# Microcontroller_Schematic.net
KiCad netlist of a schematic drawn in Altium Designer
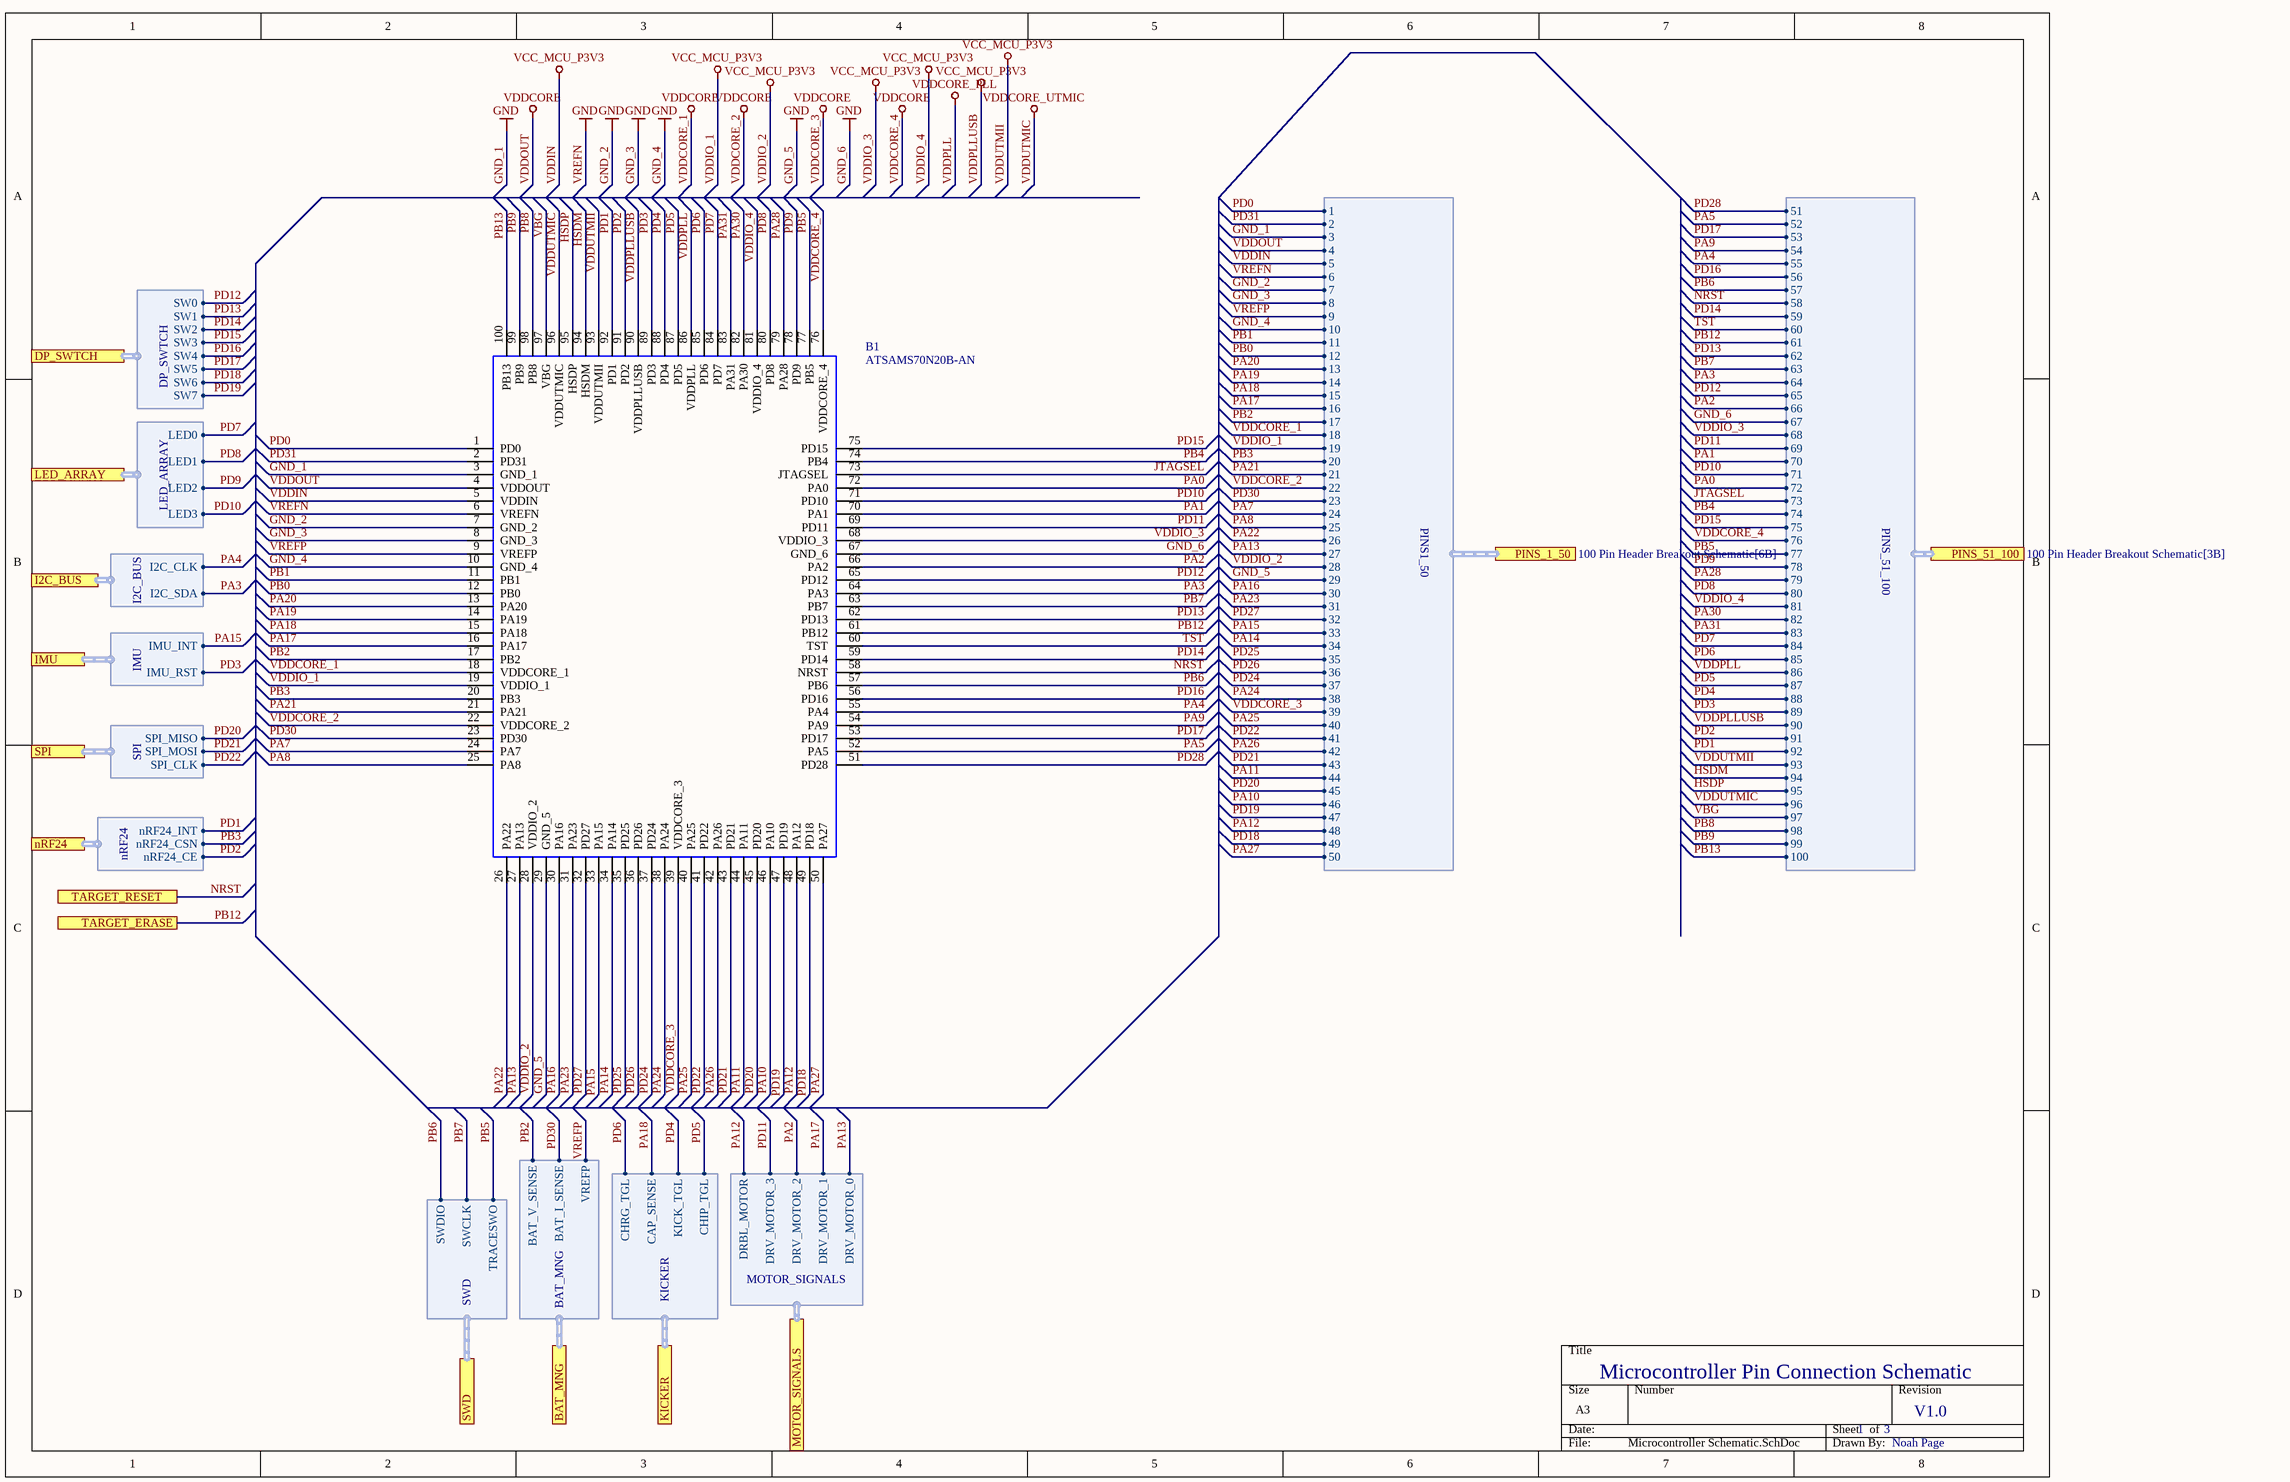
[diagram p0: Microcontroller Schematic.SchDoc]

(export (version "E")
  (design (tool "Eeschema 10.0.6"))
  (components
    (comp (ref "B1")
      (value "ATSAMS70N20B-AN")
      (footprint "QFP50P1600X1600X160-100N")
      (description "ARM Microcontrollers - MCU CM7,1024kB Flash,384kB SRAM,LQFP100")
      (fields (field (name "MOUSER PART NUMBER") "556-ATSAMS70N20B-AN"))
      (libsource (lib "Schematic Library") (part "ATSAMS70N20B-AN"))
    )
  )
  (nets
    (net (code "13") (name "/HSDM") (class "Default")
      (node (ref "B1") (pin "94") (pinfunction "HSDM_94") (pintype "passive"))
    )
    (net (code "14") (name "/HSDP") (class "Default")
      (node (ref "B1") (pin "95") (pinfunction "HSDP_95") (pintype "passive"))
    )
    (net (code "15") (name "/JTAGSEL") (class "Default")
      (node (ref "B1") (pin "73") (pinfunction "JTAGSEL_73") (pintype "passive"))
    )
    (net (code "16") (name "/NRST") (class "Default")
      (node (ref "B1") (pin "58") (pinfunction "NRST_58") (pintype "passive"))
    )
    (net (code "17") (name "/PA0") (class "Default")
      (node (ref "B1") (pin "72") (pinfunction "PA0_72") (pintype "passive"))
    )
    (net (code "18") (name "/PA1") (class "Default")
      (node (ref "B1") (pin "70") (pinfunction "PA1_70") (pintype "passive"))
    )
    (net (code "19") (name "/PA2") (class "Default")
      (node (ref "B1") (pin "66") (pinfunction "PA2_66") (pintype "passive"))
    )
    (net (code "20") (name "/PA3") (class "Default")
      (node (ref "B1") (pin "64") (pinfunction "PA3_64") (pintype "passive"))
    )
    (net (code "21") (name "/PA4") (class "Default")
      (node (ref "B1") (pin "55") (pinfunction "PA4_55") (pintype "passive"))
    )
    (net (code "22") (name "/PA5") (class "Default")
      (node (ref "B1") (pin "52") (pinfunction "PA5_52") (pintype "passive"))
    )
    (net (code "23") (name "/PA7") (class "Default")
      (node (ref "B1") (pin "24") (pinfunction "PA7_24") (pintype "passive"))
    )
    (net (code "24") (name "/PA8") (class "Default")
      (node (ref "B1") (pin "25") (pinfunction "PA8_25") (pintype "passive"))
    )
    (net (code "25") (name "/PA9") (class "Default")
      (node (ref "B1") (pin "54") (pinfunction "PA9_54") (pintype "passive"))
    )
    (net (code "26") (name "/PA10") (class "Default")
      (node (ref "B1") (pin "46") (pinfunction "PA10_46") (pintype "passive"))
    )
    (net (code "27") (name "/PA11") (class "Default")
      (node (ref "B1") (pin "44") (pinfunction "PA11_44") (pintype "passive"))
    )
    (net (code "28") (name "/PA12") (class "Default")
      (node (ref "B1") (pin "48") (pinfunction "PA12_48") (pintype "passive"))
    )
    (net (code "29") (name "/PA13") (class "Default")
      (node (ref "B1") (pin "27") (pinfunction "PA13_27") (pintype "passive"))
    )
    (net (code "30") (name "/PA14") (class "Default")
      (node (ref "B1") (pin "34") (pinfunction "PA14_34") (pintype "passive"))
    )
    (net (code "31") (name "/PA15") (class "Default")
      (node (ref "B1") (pin "33") (pinfunction "PA15_33") (pintype "passive"))
    )
    (net (code "32") (name "/PA16") (class "Default")
      (node (ref "B1") (pin "30") (pinfunction "PA16_30") (pintype "passive"))
    )
    (net (code "33") (name "/PA17") (class "Default")
      (node (ref "B1") (pin "16") (pinfunction "PA17_16") (pintype "passive"))
    )
    (net (code "34") (name "/PA18") (class "Default")
      (node (ref "B1") (pin "15") (pinfunction "PA18_15") (pintype "passive"))
    )
    (net (code "35") (name "/PA19") (class "Default")
      (node (ref "B1") (pin "14") (pinfunction "PA19_14") (pintype "passive"))
    )
    (net (code "36") (name "/PA20") (class "Default")
      (node (ref "B1") (pin "13") (pinfunction "PA20_13") (pintype "passive"))
    )
    (net (code "37") (name "/PA21") (class "Default")
      (node (ref "B1") (pin "21") (pinfunction "PA21_21") (pintype "passive"))
    )
    (net (code "38") (name "/PA22") (class "Default")
      (node (ref "B1") (pin "26") (pinfunction "PA22_26") (pintype "passive"))
    )
    (net (code "39") (name "/PA23") (class "Default")
      (node (ref "B1") (pin "31") (pinfunction "PA23_31") (pintype "passive"))
    )
    (net (code "40") (name "/PA24") (class "Default")
      (node (ref "B1") (pin "38") (pinfunction "PA24_38") (pintype "passive"))
    )
    (net (code "41") (name "/PA25") (class "Default")
      (node (ref "B1") (pin "40") (pinfunction "PA25_40") (pintype "passive"))
    )
    (net (code "42") (name "/PA26") (class "Default")
      (node (ref "B1") (pin "42") (pinfunction "PA26_42") (pintype "passive"))
    )
    (net (code "43") (name "/PA27") (class "Default")
      (node (ref "B1") (pin "50") (pinfunction "PA27_50") (pintype "passive"))
    )
    (net (code "44") (name "/PA28") (class "Default")
      (node (ref "B1") (pin "79") (pinfunction "PA28_79") (pintype "passive"))
    )
    (net (code "45") (name "/PA30") (class "Default")
      (node (ref "B1") (pin "82") (pinfunction "PA30_82") (pintype "passive"))
    )
    (net (code "46") (name "/PA31") (class "Default")
      (node (ref "B1") (pin "83") (pinfunction "PA31_83") (pintype "passive"))
    )
    (net (code "47") (name "/PB0") (class "Default")
      (node (ref "B1") (pin "12") (pinfunction "PB0_12") (pintype "passive"))
    )
    (net (code "48") (name "/PB1") (class "Default")
      (node (ref "B1") (pin "11") (pinfunction "PB1_11") (pintype "passive"))
    )
    (net (code "49") (name "/PB2") (class "Default")
      (node (ref "B1") (pin "17") (pinfunction "PB2_17") (pintype "passive"))
    )
    (net (code "50") (name "/PB3") (class "Default")
      (node (ref "B1") (pin "20") (pinfunction "PB3_20") (pintype "passive"))
    )
    (net (code "51") (name "/PB4") (class "Default")
      (node (ref "B1") (pin "74") (pinfunction "PB4_74") (pintype "passive"))
    )
    (net (code "52") (name "/PB5") (class "Default")
      (node (ref "B1") (pin "77") (pinfunction "PB5_77") (pintype "passive"))
    )
    (net (code "53") (name "/PB6") (class "Default")
      (node (ref "B1") (pin "57") (pinfunction "PB6_57") (pintype "passive"))
    )
    (net (code "54") (name "/PB7") (class "Default")
      (node (ref "B1") (pin "63") (pinfunction "PB7_63") (pintype "passive"))
    )
    (net (code "55") (name "/PB8") (class "Default")
      (node (ref "B1") (pin "98") (pinfunction "PB8_98") (pintype "passive"))
    )
    (net (code "56") (name "/PB9") (class "Default")
      (node (ref "B1") (pin "99") (pinfunction "PB9_99") (pintype "passive"))
    )
    (net (code "57") (name "/PB12") (class "Default")
      (node (ref "B1") (pin "61") (pinfunction "PB12_61") (pintype "passive"))
    )
    (net (code "58") (name "/PB13") (class "Default")
      (node (ref "B1") (pin "100") (pinfunction "PB13_100") (pintype "passive"))
    )
    (net (code "59") (name "/PD0") (class "Default")
      (node (ref "B1") (pin "1") (pinfunction "PD0_1") (pintype "passive"))
    )
    (net (code "60") (name "/PD1") (class "Default")
      (node (ref "B1") (pin "92") (pinfunction "PD1_92") (pintype "passive"))
    )
    (net (code "61") (name "/PD2") (class "Default")
      (node (ref "B1") (pin "91") (pinfunction "PD2_91") (pintype "passive"))
    )
    (net (code "62") (name "/PD3") (class "Default")
      (node (ref "B1") (pin "89") (pinfunction "PD3_89") (pintype "passive"))
    )
    (net (code "63") (name "/PD4") (class "Default")
      (node (ref "B1") (pin "88") (pinfunction "PD4_88") (pintype "passive"))
    )
    (net (code "64") (name "/PD5") (class "Default")
      (node (ref "B1") (pin "87") (pinfunction "PD5_87") (pintype "passive"))
    )
    (net (code "65") (name "/PD6") (class "Default")
      (node (ref "B1") (pin "85") (pinfunction "PD6_85") (pintype "passive"))
    )
    (net (code "66") (name "/PD7") (class "Default")
      (node (ref "B1") (pin "84") (pinfunction "PD7_84") (pintype "passive"))
    )
    (net (code "67") (name "/PD8") (class "Default")
      (node (ref "B1") (pin "80") (pinfunction "PD8_80") (pintype "passive"))
    )
    (net (code "68") (name "/PD9") (class "Default")
      (node (ref "B1") (pin "78") (pinfunction "PD9_78") (pintype "passive"))
    )
    (net (code "69") (name "/PD10") (class "Default")
      (node (ref "B1") (pin "71") (pinfunction "PD10_71") (pintype "passive"))
    )
    (net (code "70") (name "/PD11") (class "Default")
      (node (ref "B1") (pin "69") (pinfunction "PD11_69") (pintype "passive"))
    )
    (net (code "71") (name "/PD12") (class "Default")
      (node (ref "B1") (pin "65") (pinfunction "PD12_65") (pintype "passive"))
    )
    (net (code "72") (name "/PD13") (class "Default")
      (node (ref "B1") (pin "62") (pinfunction "PD13_62") (pintype "passive"))
    )
    (net (code "73") (name "/PD14") (class "Default")
      (node (ref "B1") (pin "59") (pinfunction "PD14_59") (pintype "passive"))
    )
    (net (code "74") (name "/PD15") (class "Default")
      (node (ref "B1") (pin "75") (pinfunction "PD15_75") (pintype "passive"))
    )
    (net (code "75") (name "/PD16") (class "Default")
      (node (ref "B1") (pin "56") (pinfunction "PD16_56") (pintype "passive"))
    )
    (net (code "76") (name "/PD17") (class "Default")
      (node (ref "B1") (pin "53") (pinfunction "PD17_53") (pintype "passive"))
    )
    (net (code "77") (name "/PD18") (class "Default")
      (node (ref "B1") (pin "49") (pinfunction "PD18_49") (pintype "passive"))
    )
    (net (code "78") (name "/PD19") (class "Default")
      (node (ref "B1") (pin "47") (pinfunction "PD19_47") (pintype "passive"))
    )
    (net (code "79") (name "/PD20") (class "Default")
      (node (ref "B1") (pin "45") (pinfunction "PD20_45") (pintype "passive"))
    )
    (net (code "80") (name "/PD21") (class "Default")
      (node (ref "B1") (pin "43") (pinfunction "PD21_43") (pintype "passive"))
    )
    (net (code "81") (name "/PD22") (class "Default")
      (node (ref "B1") (pin "41") (pinfunction "PD22_41") (pintype "passive"))
    )
    (net (code "82") (name "/PD24") (class "Default")
      (node (ref "B1") (pin "37") (pinfunction "PD24_37") (pintype "passive"))
    )
    (net (code "83") (name "/PD25") (class "Default")
      (node (ref "B1") (pin "35") (pinfunction "PD25_35") (pintype "passive"))
    )
    (net (code "84") (name "/PD26") (class "Default")
      (node (ref "B1") (pin "36") (pinfunction "PD26_36") (pintype "passive"))
    )
    (net (code "85") (name "/PD27") (class "Default")
      (node (ref "B1") (pin "32") (pinfunction "PD27_32") (pintype "passive"))
    )
    (net (code "86") (name "/PD28") (class "Default")
      (node (ref "B1") (pin "51") (pinfunction "PD28_51") (pintype "passive"))
    )
    (net (code "87") (name "/PD30") (class "Default")
      (node (ref "B1") (pin "23") (pinfunction "PD30_23") (pintype "passive"))
    )
    (net (code "88") (name "/PD31") (class "Default")
      (node (ref "B1") (pin "2") (pinfunction "PD31_2") (pintype "passive"))
    )
    (net (code "89") (name "/TST") (class "Default")
      (node (ref "B1") (pin "60") (pinfunction "TST_60") (pintype "passive"))
    )
    (net (code "90") (name "/VBG") (class "Default")
      (node (ref "B1") (pin "97") (pinfunction "VBG_97") (pintype "passive"))
    )
    (net (code "91") (name "/VREFP") (class "Default")
      (node (ref "B1") (pin "9") (pinfunction "VREFP_9") (pintype "passive"))
    )
    (net (code "104") (name "GND") (class "Default")
      (node (ref "B1") (pin "10") (pinfunction "GND_4_10") (pintype "passive"))
      (node (ref "B1") (pin "29") (pinfunction "GND_5_29") (pintype "passive"))
      (node (ref "B1") (pin "3") (pinfunction "GND_1_3") (pintype "passive"))
      (node (ref "B1") (pin "6") (pinfunction "VREFN_6") (pintype "passive"))
      (node (ref "B1") (pin "67") (pinfunction "GND_6_67") (pintype "passive"))
      (node (ref "B1") (pin "7") (pinfunction "GND_2_7") (pintype "passive"))
      (node (ref "B1") (pin "8") (pinfunction "GND_3_8") (pintype "passive"))
    )
    (net (code "105") (name "VCC_MCU_P3V3") (class "Default")
      (node (ref "B1") (pin "19") (pinfunction "VDDIO_1_19") (pintype "passive"))
      (node (ref "B1") (pin "28") (pinfunction "VDDIO_2_28") (pintype "passive"))
      (node (ref "B1") (pin "5") (pinfunction "VDDIN_5") (pintype "passive"))
      (node (ref "B1") (pin "68") (pinfunction "VDDIO_3_68") (pintype "passive"))
      (node (ref "B1") (pin "81") (pinfunction "VDDIO_4_81") (pintype "passive"))
      (node (ref "B1") (pin "90") (pinfunction "VDDPLLUSB_90") (pintype "passive"))
      (node (ref "B1") (pin "93") (pinfunction "VDDUTMII_93") (pintype "passive"))
    )
    (net (code "106") (name "VDDCORE") (class "Default")
      (node (ref "B1") (pin "18") (pinfunction "VDDCORE_1_18") (pintype "passive"))
      (node (ref "B1") (pin "22") (pinfunction "VDDCORE_2_22") (pintype "passive"))
      (node (ref "B1") (pin "39") (pinfunction "VDDCORE_3_39") (pintype "passive"))
      (node (ref "B1") (pin "4") (pinfunction "VDDOUT_4") (pintype "passive"))
      (node (ref "B1") (pin "76") (pinfunction "VDDCORE_4_76") (pintype "passive"))
    )
    (net (code "107") (name "VDDCORE_PLL") (class "Default")
      (node (ref "B1") (pin "86") (pinfunction "VDDPLL_86") (pintype "passive"))
    )
    (net (code "108") (name "VDDCORE_UTMIC") (class "Default")
      (node (ref "B1") (pin "96") (pinfunction "VDDUTMIC_96") (pintype "passive"))
    )
  )
)
